# ProPrj_GeniusGateway_2025-07-29.net
KiCad netlist of a schematic drawn in EasyEDA Pro
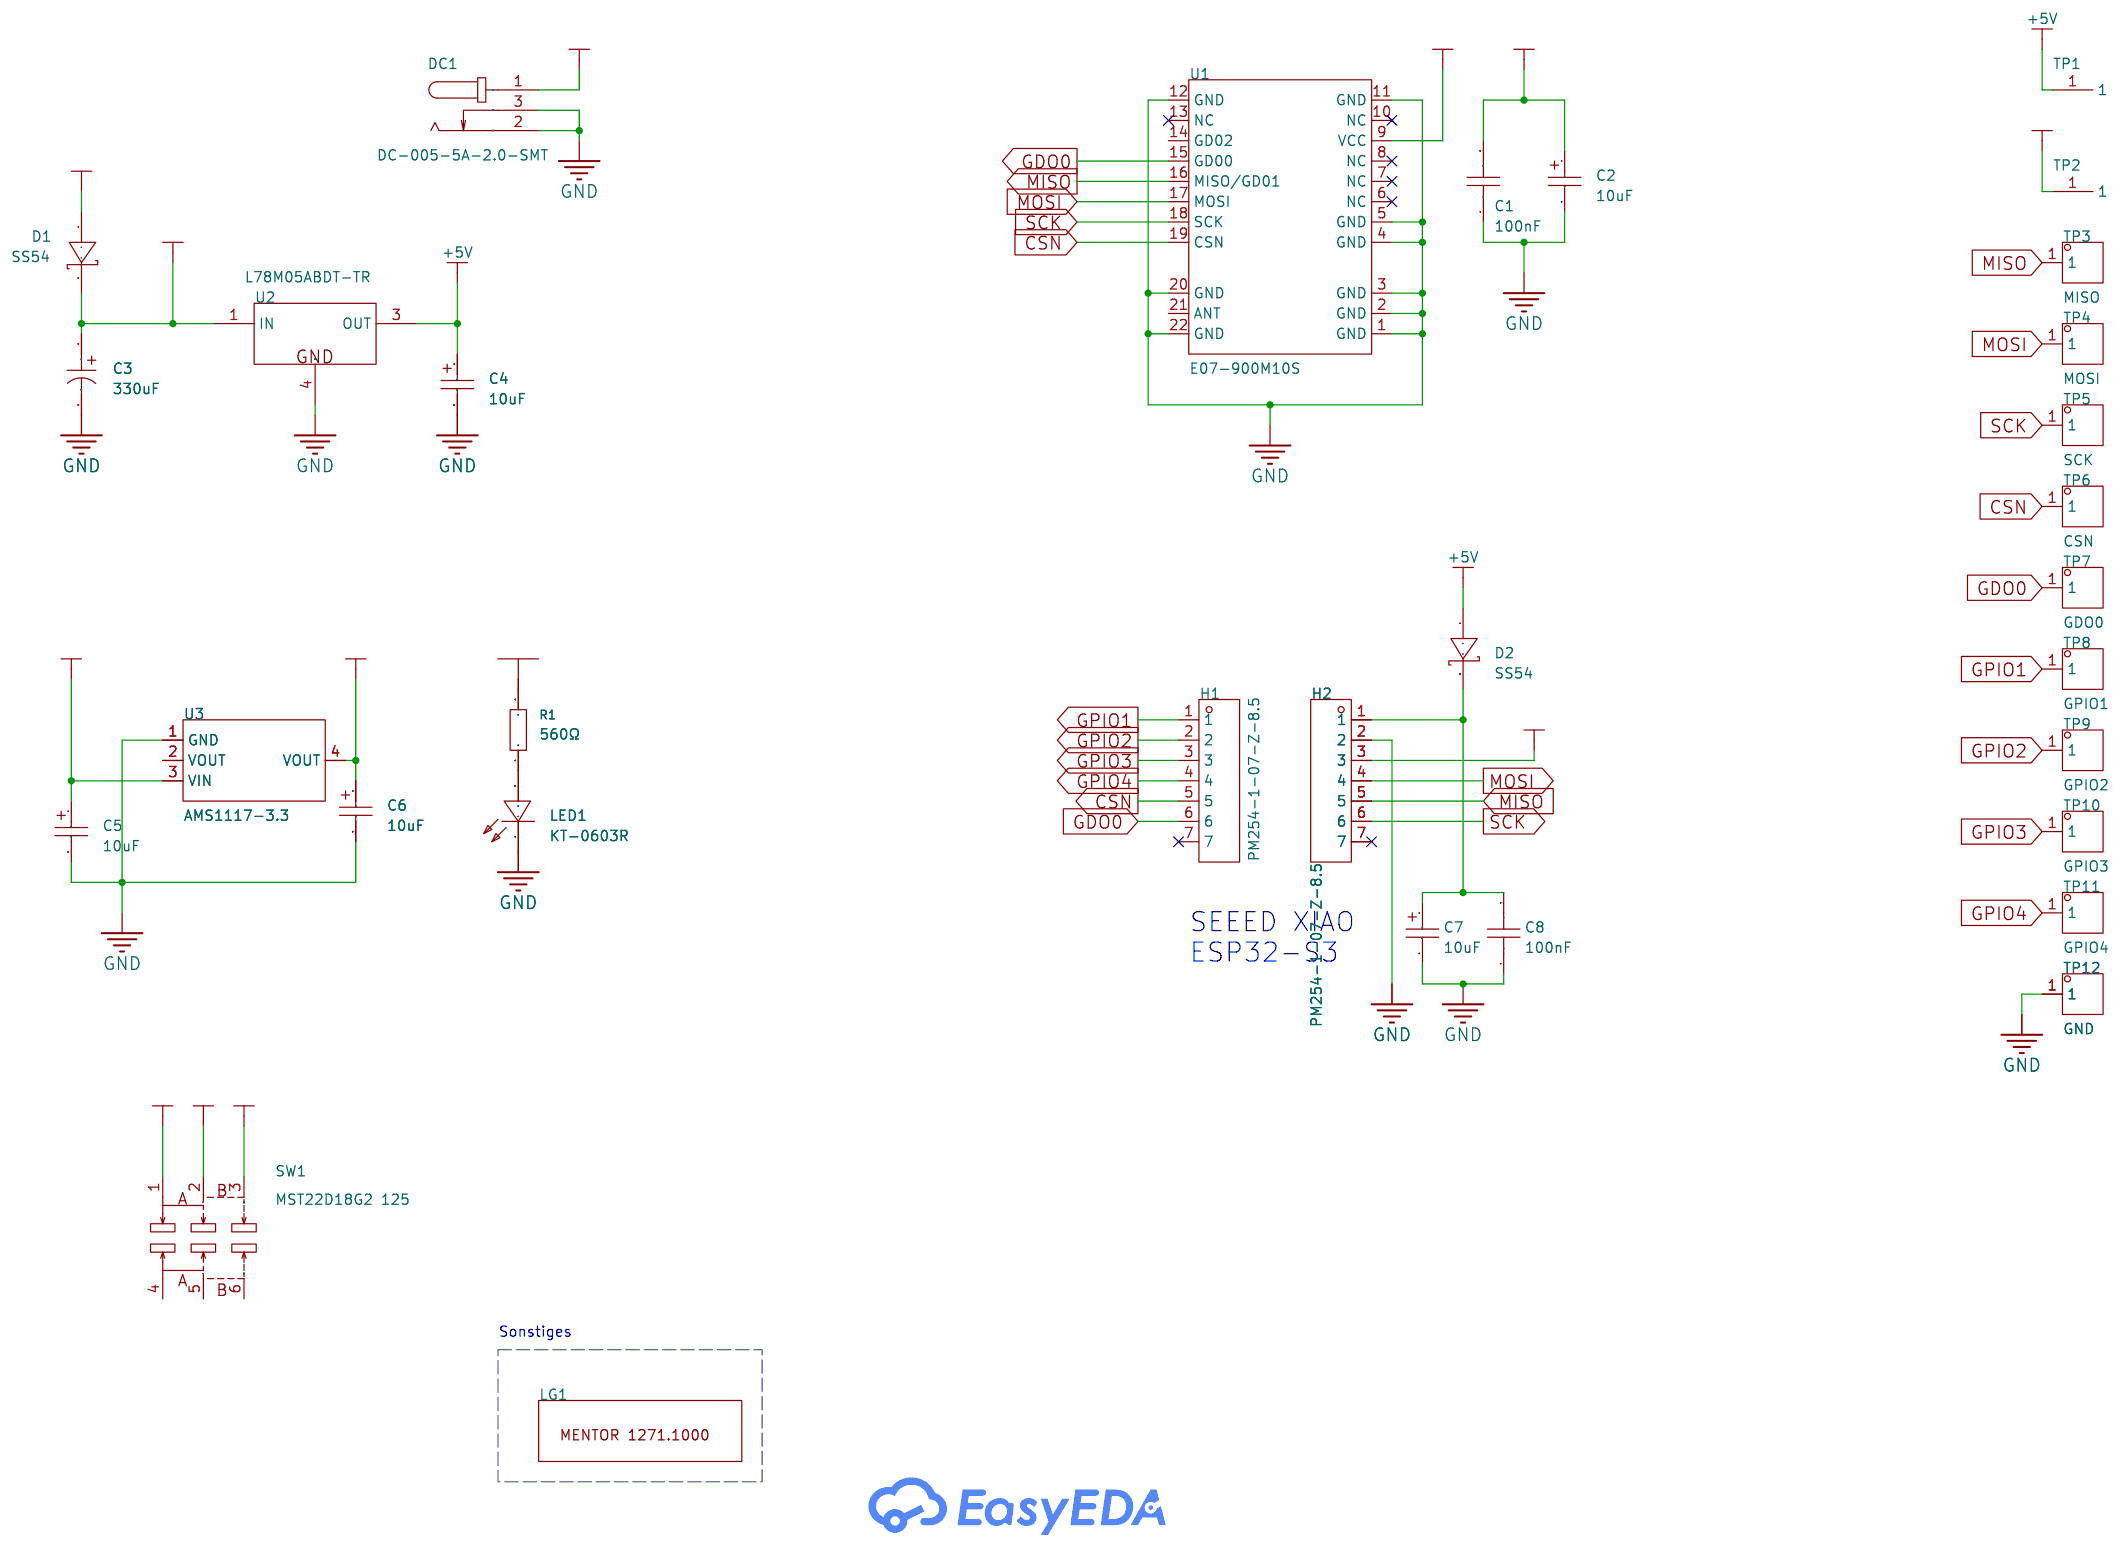
[diagram p0: schematic sheet]

(export (version "E")
  (design (tool "Eeschema 10.0.6"))
  (components
    (comp (ref "C1")
      (value "100nF")
      (footprint "easyedapro:C0805")
      (fields
        (field (name "Manufacturer Part") "CC0805KRX7R9BB104")
        (field (name "Manufacturer") "YAGEO(国巨)")
      )
      (libsource (lib "easyedapro") (part "CC0805KRX7R9BB104"))
    )
    (comp (ref "C2")
      (value "10uF")
      (footprint "easyedapro:CAP-SMD_L3.2-W1.6-RD-C7171")
      (fields (field (name "Manufacturer Part") "TAJA106K016RNJ") (field (name "Manufacturer") "Kyocera AVX"))
      (libsource (lib "easyedapro") (part "TAJA106K016RNJ"))
    )
    (comp (ref "C3")
      (value "330uF")
      (footprint "easyedapro:CAP-SMD_BD6.3-L6.6-W6.6-LS7.6-RD")
      (fields (field (name "Manufacturer Part") "189RV0016") (field (name "Manufacturer") "KNSCHA(科尼盛)"))
      (libsource (lib "easyedapro") (part "189RV0016"))
    )
    (comp (ref "C4")
      (value "10uF")
      (footprint "easyedapro:CAP-SMD_L3.2-W1.6-RD-C7171")
      (fields (field (name "Manufacturer Part") "TAJA106K016RNJ") (field (name "Manufacturer") "Kyocera AVX"))
      (libsource (lib "easyedapro") (part "TAJA106K016RNJ"))
    )
    (comp (ref "C5")
      (value "10uF")
      (footprint "easyedapro:CAP-SMD_L3.2-W1.6-RD-C7171")
      (fields (field (name "Manufacturer Part") "TAJA106K016RNJ") (field (name "Manufacturer") "Kyocera AVX"))
      (libsource (lib "easyedapro") (part "TAJA106K016RNJ"))
    )
    (comp (ref "C6")
      (value "10uF")
      (footprint "easyedapro:CAP-SMD_L3.2-W1.6-RD-C7171")
      (fields (field (name "Manufacturer Part") "TAJA106K016RNJ") (field (name "Manufacturer") "Kyocera AVX"))
      (libsource (lib "easyedapro") (part "TAJA106K016RNJ"))
    )
    (comp (ref "C7")
      (value "10uF")
      (footprint "easyedapro:CAP-SMD_L3.2-W1.6-RD-C7171")
      (fields (field (name "Manufacturer Part") "TAJA106K016RNJ") (field (name "Manufacturer") "Kyocera AVX"))
      (libsource (lib "easyedapro") (part "TAJA106K016RNJ"))
    )
    (comp (ref "C8")
      (value "100nF")
      (footprint "easyedapro:C0805")
      (fields
        (field (name "Manufacturer Part") "CC0805KRX7R9BB104")
        (field (name "Manufacturer") "YAGEO(国巨)")
      )
      (libsource (lib "easyedapro") (part "CC0805KRX7R9BB104"))
    )
    (comp (ref "D1")
      (value "SS54")
      (footprint "easyedapro:SMA_L4.4-W2.8-LS5.4-R-RD")
      (fields (field (name "Manufacturer") "MDD(辰达半导体)"))
      (libsource (lib "easyedapro") (part "SS54_C22452"))
    )
    (comp (ref "D2")
      (value "SS54")
      (footprint "easyedapro:SMA_L4.4-W2.8-LS5.4-R-RD")
      (fields (field (name "Manufacturer") "MDD(辰达半导体)"))
      (libsource (lib "easyedapro") (part "SS54_C22452"))
    )
    (comp (ref "DC1")
      (value "DC-005-5A-2.0-SMT")
      (footprint "easyedapro:DC-IN-TH_DC-005-5A-2.0-SMT")
      (fields (field (name "Manufacturer") "XKB Connection(中国星坤)"))
      (libsource (lib "easyedapro") (part "DC-005-5A-2.0-SMT"))
    )
    (comp (ref "H1")
      (value "PM254-1-07-Z-8.5")
      (footprint "easyedapro:HDR-TH_7P-P2.54-V-F")
      (fields (field (name "Manufacturer") "HCTL(华灿天禄)"))
      (libsource (lib "easyedapro") (part "PM254-1-07-Z-8.5"))
    )
    (comp (ref "H2")
      (value "PM254-1-07-Z-8.5")
      (footprint "easyedapro:HDR-TH_7P-P2.54-V-F")
      (fields (field (name "Manufacturer") "HCTL(华灿天禄)"))
      (libsource (lib "easyedapro") (part "PM254-1-07-Z-8.5"))
    )
    (comp (ref "LED1")
      (value "KT-0603R")
      (footprint "easyedapro:LED0603-RD")
      (fields (field (name "Manufacturer") "KENTO"))
      (libsource (lib "easyedapro") (part "KT-0603R"))
    )
    (comp (ref "LG1")
      (value "~")
      (footprint "easyedapro:MENTOR-1271.1000")
      (description "MENTOR 1271.1000")
      (libsource (lib "easyedapro") (part "Lightguide 1"))
    )
    (comp (ref "R1")
      (value "560Ω")
      (footprint "easyedapro:R0603")
      (fields
        (field (name "Manufacturer Part") "0603WAF5600T5E")
        (field (name "Manufacturer") "UNI-ROYAL(厚声)")
      )
      (libsource (lib "easyedapro") (part "0603WAF5600T5E"))
    )
    (comp (ref "SW1")
      (value "MST22D18G2 125")
      (footprint "easyedapro:SW-SMD_MST22D18G2")
      (fields (field (name "Manufacturer") "SHOU HAN(首韩)"))
      (libsource (lib "easyedapro") (part "MST22D18G2 125"))
    )
    (comp (ref "TP1")
      (value "+5V")
      (footprint "easyedapro:Testpoint_SMD_R1.5_Border")
      (libsource (lib "easyedapro") (part "Testpoint1"))
    )
    (comp (ref "TP2")
      (value "3V3")
      (footprint "easyedapro:Testpoint_SMD_R1.5_Border")
      (libsource (lib "easyedapro") (part "Testpoint1"))
    )
    (comp (ref "TP3")
      (value "MISO")
      (footprint "easyedapro:TEST-TH_BD2.54-P1.39")
      (fields (field (name "Manufacturer Part") "5001") (field (name "Manufacturer") "Keystone"))
      (libsource (lib "easyedapro") (part "5001"))
    )
    (comp (ref "TP4")
      (value "MOSI")
      (footprint "easyedapro:TEST-TH_BD2.54-P1.39")
      (fields (field (name "Manufacturer Part") "5001") (field (name "Manufacturer") "Keystone"))
      (libsource (lib "easyedapro") (part "5001"))
    )
    (comp (ref "TP5")
      (value "SCK")
      (footprint "easyedapro:TEST-TH_BD2.54-P1.39")
      (fields (field (name "Manufacturer Part") "5001") (field (name "Manufacturer") "Keystone"))
      (libsource (lib "easyedapro") (part "5001"))
    )
    (comp (ref "TP6")
      (value "CSN")
      (footprint "easyedapro:TEST-TH_BD2.54-P1.39")
      (fields (field (name "Manufacturer Part") "5001") (field (name "Manufacturer") "Keystone"))
      (libsource (lib "easyedapro") (part "5001"))
    )
    (comp (ref "TP7")
      (value "GDO0")
      (footprint "easyedapro:TEST-TH_BD2.54-P1.39")
      (fields (field (name "Manufacturer Part") "5001") (field (name "Manufacturer") "Keystone"))
      (libsource (lib "easyedapro") (part "5001"))
    )
    (comp (ref "TP8")
      (value "GPIO1")
      (footprint "easyedapro:TEST-TH_BD2.54-P1.39")
      (fields (field (name "Manufacturer Part") "5001") (field (name "Manufacturer") "Keystone"))
      (libsource (lib "easyedapro") (part "5001"))
    )
    (comp (ref "TP9")
      (value "GPIO2")
      (footprint "easyedapro:TEST-TH_BD2.54-P1.39")
      (fields (field (name "Manufacturer Part") "5001") (field (name "Manufacturer") "Keystone"))
      (libsource (lib "easyedapro") (part "5001"))
    )
    (comp (ref "TP10")
      (value "GPIO3")
      (footprint "easyedapro:TEST-TH_BD2.54-P1.39")
      (fields (field (name "Manufacturer Part") "5001") (field (name "Manufacturer") "Keystone"))
      (libsource (lib "easyedapro") (part "5001"))
    )
    (comp (ref "TP11")
      (value "GPIO4")
      (footprint "easyedapro:TEST-TH_BD2.54-P1.39")
      (fields (field (name "Manufacturer Part") "5001") (field (name "Manufacturer") "Keystone"))
      (libsource (lib "easyedapro") (part "5001"))
    )
    (comp (ref "TP12")
      (value "GND")
      (footprint "easyedapro:TEST-TH_BD2.54-P1.39")
      (fields (field (name "Manufacturer Part") "5001") (field (name "Manufacturer") "Keystone"))
      (libsource (lib "easyedapro") (part "5001"))
    )
    (comp (ref "U1")
      (value "E07-900M10S")
      (footprint "easyedapro:WIRELM-SMD_22P-L20.0-W14.0-P1.27-BR")
      (libsource (lib "easyedapro") (part "E07-900M10S"))
    )
    (comp (ref "U2")
      (value "L78M05ABDT-TR")
      (footprint "easyedapro:TO-252-2_L6.5-W6.1-P4.58-LS10.0-TL")
      (fields (field (name "Manufacturer") "ST(意法半导体)"))
      (libsource (lib "easyedapro") (part "L78M05ABDT-TR"))
    )
    (comp (ref "U3")
      (value "AMS1117-3.3")
      (footprint "easyedapro:SOT-223-3_L6.5-W3.4-P2.30-LS7.0-BR")
      (fields (field (name "Manufacturer") "AMS"))
      (libsource (lib "easyedapro") (part "AMS1117-3.3"))
    )
  )
  (nets
    (net (code "1") (name "+3V3") (class "Default")
      (node (ref "C1") (pin "2") (pinfunction "2_2") (pintype "unspecified"))
      (node (ref "C2") (pin "1") (pinfunction "1_1") (pintype "input"))
      (node (ref "R1") (pin "2") (pinfunction "2_2") (pintype "input"))
      (node (ref "SW1") (pin "2") (pinfunction "2_2") (pintype "unspecified"))
      (node (ref "TP2") (pin "1") (pinfunction "1_1") (pintype "input"))
      (node (ref "U1") (pin "9") (pinfunction "VCC_9") (pintype "unspecified"))
    )
    (net (code "2") (name "+3V3-LDO") (class "Default")
      (node (ref "C6") (pin "1") (pinfunction "1_1") (pintype "input"))
      (node (ref "SW1") (pin "1") (pinfunction "1_1") (pintype "unspecified"))
      (node (ref "U3") (pin "4") (pinfunction "VOUT_4") (pintype "unspecified"))
    )
    (net (code "3") (name "+3V3-XIAO") (class "Default")
      (node (ref "H2") (pin "3") (pinfunction "3_3") (pintype "unspecified"))
      (node (ref "SW1") (pin "3") (pinfunction "3_3") (pintype "unspecified"))
    )
    (net (code "4") (name "+5V") (class "Default")
      (node (ref "C4") (pin "1") (pinfunction "1_1") (pintype "input"))
      (node (ref "C5") (pin "1") (pinfunction "1_1") (pintype "input"))
      (node (ref "D2") (pin "1") (pinfunction "A_1") (pintype "unspecified"))
      (node (ref "TP1") (pin "1") (pinfunction "1_1") (pintype "input"))
      (node (ref "U2") (pin "3") (pinfunction "OUT_3") (pintype "unspecified"))
      (node (ref "U3") (pin "3") (pinfunction "VIN_3") (pintype "unspecified"))
    )
    (net (code "5") (name "+12V") (class "Default")
      (node (ref "C3") (pin "1") (pinfunction "1_1") (pintype "input"))
      (node (ref "D1") (pin "2") (pinfunction "K_2") (pintype "unspecified"))
      (node (ref "U2") (pin "1") (pinfunction "IN_1") (pintype "unspecified"))
    )
    (net (code "6") (name "+12V_IN") (class "Default")
      (node (ref "D1") (pin "1") (pinfunction "A_1") (pintype "unspecified"))
      (node (ref "DC1") (pin "1") (pinfunction "1_1") (pintype "unspecified"))
    )
    (net (code "7") (name "CSN") (class "Default")
      (node (ref "H1") (pin "5") (pinfunction "5_5") (pintype "unspecified"))
      (node (ref "TP6") (pin "1") (pinfunction "1_1") (pintype "unspecified"))
      (node (ref "U1") (pin "19") (pinfunction "CSN_19") (pintype "unspecified"))
    )
    (net (code "8") (name "GDO0") (class "Default")
      (node (ref "H1") (pin "6") (pinfunction "6_6") (pintype "unspecified"))
      (node (ref "TP7") (pin "1") (pinfunction "1_1") (pintype "unspecified"))
      (node (ref "U1") (pin "15") (pinfunction "GD00_15") (pintype "unspecified"))
    )
    (net (code "9") (name "GND") (class "Default")
      (node (ref "C1") (pin "1") (pinfunction "1_1") (pintype "unspecified"))
      (node (ref "C2") (pin "2") (pinfunction "2_2") (pintype "input"))
      (node (ref "C3") (pin "2") (pinfunction "2_2") (pintype "input"))
      (node (ref "C4") (pin "2") (pinfunction "2_2") (pintype "input"))
      (node (ref "C5") (pin "2") (pinfunction "2_2") (pintype "input"))
      (node (ref "C6") (pin "2") (pinfunction "2_2") (pintype "input"))
      (node (ref "C7") (pin "2") (pinfunction "2_2") (pintype "input"))
      (node (ref "C8") (pin "1") (pinfunction "1_1") (pintype "unspecified"))
      (node (ref "DC1") (pin "2") (pinfunction "2_2") (pintype "unspecified"))
      (node (ref "DC1") (pin "3") (pinfunction "3_3") (pintype "unspecified"))
      (node (ref "H2") (pin "2") (pinfunction "2_2") (pintype "unspecified"))
      (node (ref "LED1") (pin "1") (pinfunction "K_1") (pintype "unspecified"))
      (node (ref "TP12") (pin "1") (pinfunction "1_1") (pintype "unspecified"))
      (node (ref "U1") (pin "1") (pinfunction "GND_1") (pintype "unspecified"))
      (node (ref "U1") (pin "11") (pinfunction "GND_11") (pintype "unspecified"))
      (node (ref "U1") (pin "12") (pinfunction "GND_12") (pintype "unspecified"))
      (node (ref "U1") (pin "2") (pinfunction "GND_2") (pintype "unspecified"))
      (node (ref "U1") (pin "20") (pinfunction "GND_20") (pintype "unspecified"))
      (node (ref "U1") (pin "22") (pinfunction "GND_22") (pintype "unspecified"))
      (node (ref "U1") (pin "3") (pinfunction "GND_3") (pintype "unspecified"))
      (node (ref "U1") (pin "4") (pinfunction "GND_4") (pintype "unspecified"))
      (node (ref "U1") (pin "5") (pinfunction "GND_5") (pintype "unspecified"))
      (node (ref "U2") (pin "4") (pinfunction "GND_4") (pintype "unspecified"))
      (node (ref "U3") (pin "1") (pinfunction "GND_1") (pintype "unspecified"))
    )
    (net (code "10") (name "GPIO1") (class "Default")
      (node (ref "H1") (pin "1") (pinfunction "1_1") (pintype "unspecified"))
      (node (ref "TP8") (pin "1") (pinfunction "1_1") (pintype "unspecified"))
    )
    (net (code "11") (name "GPIO2") (class "Default")
      (node (ref "H1") (pin "2") (pinfunction "2_2") (pintype "unspecified"))
      (node (ref "TP9") (pin "1") (pinfunction "1_1") (pintype "unspecified"))
    )
    (net (code "12") (name "GPIO3") (class "Default")
      (node (ref "H1") (pin "3") (pinfunction "3_3") (pintype "unspecified"))
      (node (ref "TP10") (pin "1") (pinfunction "1_1") (pintype "unspecified"))
    )
    (net (code "13") (name "GPIO4") (class "Default")
      (node (ref "H1") (pin "4") (pinfunction "4_4") (pintype "unspecified"))
      (node (ref "TP11") (pin "1") (pinfunction "1_1") (pintype "unspecified"))
    )
    (net (code "14") (name "MISO") (class "Default")
      (node (ref "H2") (pin "5") (pinfunction "5_5") (pintype "unspecified"))
      (node (ref "TP3") (pin "1") (pinfunction "1_1") (pintype "unspecified"))
      (node (ref "U1") (pin "16") (pinfunction "MISO/GD01_16") (pintype "unspecified"))
    )
    (net (code "15") (name "MOSI") (class "Default")
      (node (ref "H2") (pin "4") (pinfunction "4_4") (pintype "unspecified"))
      (node (ref "TP4") (pin "1") (pinfunction "1_1") (pintype "unspecified"))
      (node (ref "U1") (pin "17") (pinfunction "MOSI_17") (pintype "unspecified"))
    )
    (net (code "16") (name "Net-(D2-K)") (class "Default")
      (node (ref "C7") (pin "1") (pinfunction "1_1") (pintype "input"))
      (node (ref "C8") (pin "2") (pinfunction "2_2") (pintype "unspecified"))
      (node (ref "D2") (pin "2") (pinfunction "K_2") (pintype "unspecified"))
      (node (ref "H2") (pin "1") (pinfunction "1_1") (pintype "unspecified"))
    )
    (net (code "17") (name "Net-(LED1-A)") (class "Default")
      (node (ref "LED1") (pin "2") (pinfunction "A_2") (pintype "unspecified"))
      (node (ref "R1") (pin "1") (pinfunction "1_1") (pintype "input"))
    )
    (net (code "18") (name "SCK") (class "Default")
      (node (ref "H2") (pin "6") (pinfunction "6_6") (pintype "unspecified"))
      (node (ref "TP5") (pin "1") (pinfunction "1_1") (pintype "unspecified"))
      (node (ref "U1") (pin "18") (pinfunction "SCK_18") (pintype "unspecified"))
    )
    (net (code "19") (name "unconnected-(H1-Pad7)") (class "Default")
      (node (ref "H1") (pin "7") (pinfunction "7_7") (pintype "unspecified+no_connect"))
    )
    (net (code "20") (name "unconnected-(H2-Pad7)") (class "Default")
      (node (ref "H2") (pin "7") (pinfunction "7_7") (pintype "unspecified+no_connect"))
    )
    (net (code "21") (name "unconnected-(SW1-Pad4)") (class "Default")
      (node (ref "SW1") (pin "4") (pinfunction "4_4") (pintype "unspecified"))
    )
    (net (code "22") (name "unconnected-(SW1-Pad5)") (class "Default")
      (node (ref "SW1") (pin "5") (pinfunction "5_5") (pintype "unspecified"))
    )
    (net (code "23") (name "unconnected-(SW1-Pad6)") (class "Default")
      (node (ref "SW1") (pin "6") (pinfunction "6_6") (pintype "unspecified"))
    )
    (net (code "24") (name "unconnected-(U1-ANT-Pad21)") (class "Default")
      (node (ref "U1") (pin "21") (pinfunction "ANT_21") (pintype "unspecified"))
    )
    (net (code "25") (name "unconnected-(U1-GD02-Pad14)") (class "Default")
      (node (ref "U1") (pin "14") (pinfunction "GD02_14") (pintype "unspecified"))
    )
    (net (code "26") (name "unconnected-(U1-NC-Pad6)") (class "Default")
      (node (ref "U1") (pin "6") (pinfunction "NC_6") (pintype "unspecified+no_connect"))
    )
    (net (code "27") (name "unconnected-(U1-NC-Pad7)") (class "Default")
      (node (ref "U1") (pin "7") (pinfunction "NC_7") (pintype "unspecified+no_connect"))
    )
    (net (code "28") (name "unconnected-(U1-NC-Pad8)") (class "Default")
      (node (ref "U1") (pin "8") (pinfunction "NC_8") (pintype "unspecified+no_connect"))
    )
    (net (code "29") (name "unconnected-(U1-NC-Pad10)") (class "Default")
      (node (ref "U1") (pin "10") (pinfunction "NC_10") (pintype "unspecified+no_connect"))
    )
    (net (code "30") (name "unconnected-(U1-NC-Pad13)") (class "Default")
      (node (ref "U1") (pin "13") (pinfunction "NC_13") (pintype "unspecified+no_connect"))
    )
    (net (code "31") (name "unconnected-(U3-VOUT-Pad2)") (class "Default")
      (node (ref "U3") (pin "2") (pinfunction "VOUT_2") (pintype "unspecified"))
    )
  )
)
